# 2_Non_Volatile_Memories.net
KiCad netlist of a schematic drawn in Altium Designer
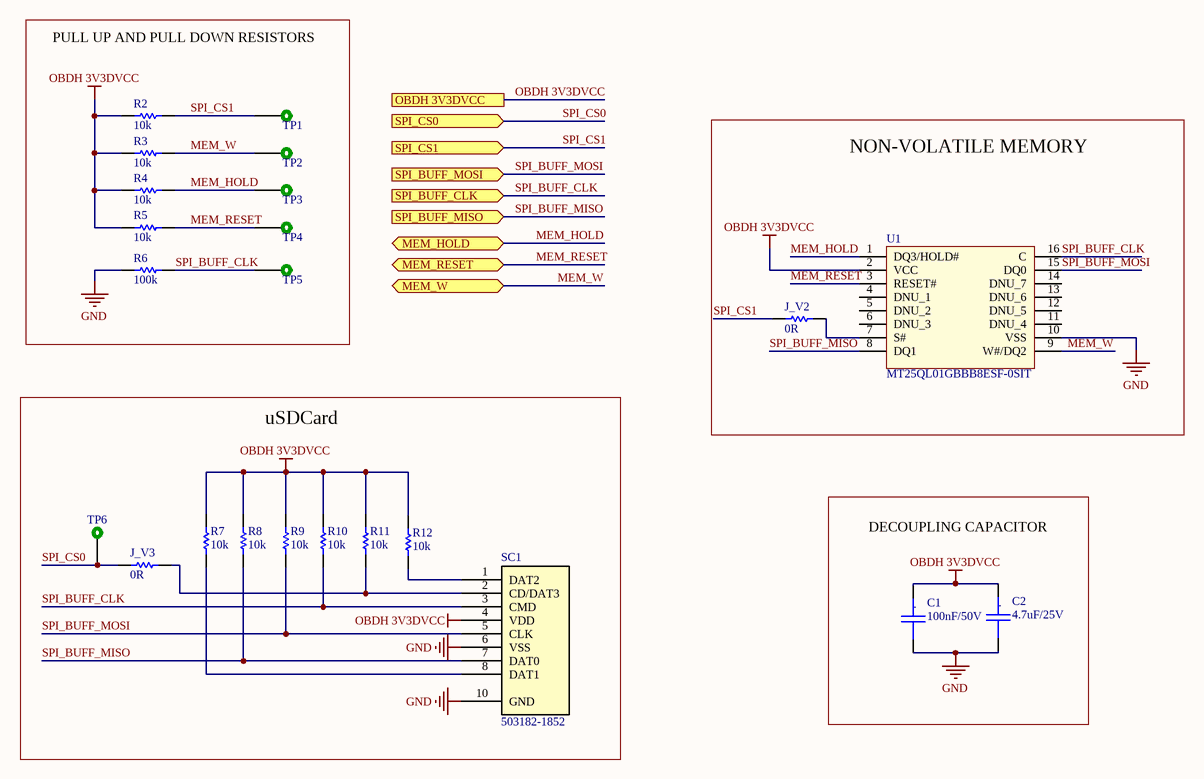
[diagram p0: 2_Non_Volatile_Memories.SchDoc]

(export (version "E")
  (design (tool "Eeschema 10.0.6"))
  (components
    (comp (ref "C1")
      (value "100nF/50V")
      (footprint "C0603_MD")
      (description "CAP CER 100nF 50V 0603 10%")
      (fields (field (name "PARTNUMBER") "C0603C104K5RAC3121") (field (name "MANUFACTURER") "Yageo"))
      (libsource (lib "Memory_Expansion_Daughter_Board_SchLib") (part "Cap_Cer_X7R_100nF_50V_0603"))
    )
    (comp (ref "C2")
      (value "4.7uF/25V")
      (footprint "C0805_MD")
      (description "CAP CER 4.7UF 25V 10% X7R 0805")
      (fields (field (name "PARTNUMBER") "C0805C475K3RACAUTO") (field (name "MANUFACTURER") "Taiyo Yuden"))
      (libsource (lib "Memory_Expansion_Daughter_Board_SchLib") (part "Cap_Cer_X7R_4.7uF_25V_0805"))
    )
    (comp (ref "J_V2")
      (value "0R")
      (footprint "0805")
      (description "RES 0R OHM 1/8W JUMPER 0805")
      (fields (field (name "PARTNUMBER") "CRCW08050000Z0EA") (field (name "MANUFACTURER") "Yageo"))
      (libsource (lib "Memory_Expansion_Daughter_Board_SchLib") (part "RC0805JR-070RL"))
    )
    (comp (ref "J_V3")
      (value "0R")
      (footprint "0805")
      (description "RES 0R OHM 1/8W JUMPER 0805")
      (fields (field (name "PARTNUMBER") "CRCW08050000Z0EA") (field (name "MANUFACTURER") "Yageo"))
      (libsource (lib "Memory_Expansion_Daughter_Board_SchLib") (part "RC0805JR-070RL"))
    )
    (comp (ref "R2")
      (value "10k")
      (footprint "0805")
      (description "RES 10K OHM 1/8W 1%  0805")
      (fields (field (name "PARTNUMBER") "CRCW080510K0FKEA") (field (name "MANUFACTURER") "Vishay"))
      (libsource (lib "Memory_Expansion_Daughter_Board_SchLib") (part "R10k_1%_1/8W_0805"))
    )
    (comp (ref "R3")
      (value "10k")
      (footprint "0805")
      (description "RES 10K OHM 1/8W 1%  0805")
      (fields (field (name "PARTNUMBER") "CRCW080510K0FKEA") (field (name "MANUFACTURER") "Vishay"))
      (libsource (lib "Memory_Expansion_Daughter_Board_SchLib") (part "R10k_1%_1/8W_0805"))
    )
    (comp (ref "R4")
      (value "10k")
      (footprint "0805")
      (description "RES 10K OHM 1/8W 1%  0805")
      (fields (field (name "PARTNUMBER") "CRCW080510K0FKEA") (field (name "MANUFACTURER") "Vishay"))
      (libsource (lib "Memory_Expansion_Daughter_Board_SchLib") (part "R10k_1%_1/8W_0805"))
    )
    (comp (ref "R5")
      (value "10k")
      (footprint "0805")
      (description "RES 10K OHM 1/8W 1%  0805")
      (fields (field (name "PARTNUMBER") "CRCW080510K0FKEA") (field (name "MANUFACTURER") "Vishay"))
      (libsource (lib "Memory_Expansion_Daughter_Board_SchLib") (part "R10k_1%_1/8W_0805"))
    )
    (comp (ref "R6")
      (value "100k")
      (footprint "0805")
      (description "RES 100K OHM 1/8W 1% 0805")
      (fields (field (name "PARTNUMBER") "AC0805FR-13100KL") (field (name "MANUFACTURER") "Yageo"))
      (libsource (lib "Memory_Expansion_Daughter_Board_SchLib") (part "R100k_1%_1/8W_0805"))
    )
    (comp (ref "R7")
      (value "10k")
      (footprint "0805")
      (description "RES 10K OHM 1/8W 1%  0805")
      (fields (field (name "PARTNUMBER") "CRCW080510K0FKEA") (field (name "MANUFACTURER") "Vishay"))
      (libsource (lib "Memory_Expansion_Daughter_Board_SchLib") (part "R10k_1%_1/8W_0805"))
    )
    (comp (ref "R8")
      (value "10k")
      (footprint "0805")
      (description "RES 10K OHM 1/8W 1%  0805")
      (fields (field (name "PARTNUMBER") "CRCW080510K0FKEA") (field (name "MANUFACTURER") "Vishay"))
      (libsource (lib "Memory_Expansion_Daughter_Board_SchLib") (part "R10k_1%_1/8W_0805"))
    )
    (comp (ref "R9")
      (value "10k")
      (footprint "0805")
      (description "RES 10K OHM 1/8W 1%  0805")
      (fields (field (name "PARTNUMBER") "CRCW080510K0FKEA") (field (name "MANUFACTURER") "Vishay"))
      (libsource (lib "Memory_Expansion_Daughter_Board_SchLib") (part "R10k_1%_1/8W_0805"))
    )
    (comp (ref "R10")
      (value "10k")
      (footprint "0805")
      (description "RES 10K OHM 1/8W 1%  0805")
      (fields (field (name "PARTNUMBER") "CRCW080510K0FKEA") (field (name "MANUFACTURER") "Vishay"))
      (libsource (lib "Memory_Expansion_Daughter_Board_SchLib") (part "R10k_1%_1/8W_0805"))
    )
    (comp (ref "R11")
      (value "10k")
      (footprint "0805")
      (description "RES 10K OHM 1/8W 1%  0805")
      (fields (field (name "PARTNUMBER") "CRCW080510K0FKEA") (field (name "MANUFACTURER") "Vishay"))
      (libsource (lib "Memory_Expansion_Daughter_Board_SchLib") (part "R10k_1%_1/8W_0805"))
    )
    (comp (ref "R12")
      (value "10k")
      (footprint "0805")
      (description "RES 10K OHM 1/8W 1%  0805")
      (fields (field (name "PARTNUMBER") "CRCW080510K0FKEA") (field (name "MANUFACTURER") "Vishay"))
      (libsource (lib "Memory_Expansion_Daughter_Board_SchLib") (part "R10k_1%_1/8W_0805"))
    )
    (comp (ref "SC1")
      (value "MicroSD Card Connector")
      (footprint "USD_CARD")
      (description "MOLEX - 503182-1852 - Micro SD Normal UltraLowPro8CktEmbsTpPkg RoHS Compliant: Yes")
      (fields (field (name "MANUFACTURER") "Molex") (field (name "MANUFACTURER PART NUMBER") "503182-1852"))
      (libsource (lib "Memory_Expansion_Daughter_Board_SchLib") (part "503182-1852"))
    )
    (comp (ref "TP1")
      (value "TEST_POINT_2")
      (footprint "TEST_POINT_2")
      (description "Test point")
      (libsource (lib "Memory_Expansion_Daughter_Board_SchLib") (part "TEST_POINT_2"))
    )
    (comp (ref "TP2")
      (value "TEST_POINT_2")
      (footprint "TEST_POINT_2")
      (description "Test point")
      (libsource (lib "Memory_Expansion_Daughter_Board_SchLib") (part "TEST_POINT_2"))
    )
    (comp (ref "TP3")
      (value "TEST_POINT_2")
      (footprint "TEST_POINT_2")
      (description "Test point")
      (libsource (lib "Memory_Expansion_Daughter_Board_SchLib") (part "TEST_POINT_2"))
    )
    (comp (ref "TP4")
      (value "TEST_POINT_2")
      (footprint "TEST_POINT_2")
      (description "Test point")
      (libsource (lib "Memory_Expansion_Daughter_Board_SchLib") (part "TEST_POINT_2"))
    )
    (comp (ref "TP5")
      (value "TEST_POINT_2")
      (footprint "TEST_POINT_2")
      (description "Test point")
      (libsource (lib "Memory_Expansion_Daughter_Board_SchLib") (part "TEST_POINT_2"))
    )
    (comp (ref "TP6")
      (value "TEST_POINT_2")
      (footprint "TEST_POINT_2")
      (description "Test point")
      (libsource (lib "Memory_Expansion_Daughter_Board_SchLib") (part "TEST_POINT_2"))
    )
    (comp (ref "U1")
      (value "MT25QL01GBBB8ESF-0SIT")
      (footprint "SOIC127P1032X265-16N")
      (description "NOR Flash Serial-SPI 3V 1Gbit 1024M/512M/256M x 1bit/2bit/4bit 6ns 16-Pin SOP-II")
      (fields
        (field (name "MANUFACTURER") "Micron Technology")
        (field (name "MANUFACTURER PART NUMBER") "MT25QL01GBBB8ESF-0SIT")
      )
      (libsource (lib "Memory_Expansion_Daughter_Board_SchLib") (part "MT25QL01GBBB8ESF-0SIT (2)"))
    )
  )
  (nets
    (net (code "1") (name "/MEM_HOLD") (class "Default")
      (node (ref "R4") (pin "1") (pinfunction "1_1") (pintype "passive"))
      (node (ref "TP3") (pin "1") (pinfunction "1_1") (pintype "passive"))
      (node (ref "U1") (pin "1") (pinfunction "DQ3/HOLD#_1") (pintype "passive"))
    )
    (net (code "2") (name "/MEM_RESET") (class "Default")
      (node (ref "R5") (pin "1") (pinfunction "1_1") (pintype "passive"))
      (node (ref "TP4") (pin "1") (pinfunction "1_1") (pintype "passive"))
      (node (ref "U1") (pin "3") (pinfunction "RESET#_3") (pintype "passive"))
    )
    (net (code "3") (name "/MEM_W") (class "Default")
      (node (ref "R3") (pin "1") (pinfunction "1_1") (pintype "passive"))
      (node (ref "TP2") (pin "1") (pinfunction "1_1") (pintype "passive"))
      (node (ref "U1") (pin "9") (pinfunction "W#/DQ2_9") (pintype "passive"))
    )
    (net (code "4") (name "/SPI_BUFF_CLK") (class "Default")
      (node (ref "R10") (pin "1") (pinfunction "1_1") (pintype "passive"))
      (node (ref "R6") (pin "1") (pinfunction "1_1") (pintype "passive"))
      (node (ref "SC1") (pin "3") (pinfunction "CMD_3") (pintype "passive"))
      (node (ref "TP5") (pin "1") (pinfunction "1_1") (pintype "passive"))
      (node (ref "U1") (pin "16") (pinfunction "C_16") (pintype "passive"))
    )
    (net (code "5") (name "/SPI_BUFF_MISO") (class "Default")
      (node (ref "R8") (pin "1") (pinfunction "1_1") (pintype "passive"))
      (node (ref "SC1") (pin "7") (pinfunction "DAT0_7") (pintype "passive"))
      (node (ref "U1") (pin "8") (pinfunction "DQ1_8") (pintype "passive"))
    )
    (net (code "6") (name "/SPI_BUFF_MOSI") (class "Default")
      (node (ref "R9") (pin "1") (pinfunction "1_1") (pintype "passive"))
      (node (ref "SC1") (pin "5") (pinfunction "CLK_5") (pintype "passive"))
      (node (ref "U1") (pin "15") (pinfunction "DQ0_15") (pintype "passive"))
    )
    (net (code "7") (name "/SPI_CS0") (class "Default")
      (node (ref "J_V3") (pin "2") (pinfunction "2_2") (pintype "passive"))
      (node (ref "TP6") (pin "1") (pinfunction "1_1") (pintype "passive"))
    )
    (net (code "8") (name "/SPI_CS1") (class "Default")
      (node (ref "J_V2") (pin "2") (pinfunction "2_2") (pintype "passive"))
      (node (ref "R2") (pin "1") (pinfunction "1_1") (pintype "passive"))
      (node (ref "TP1") (pin "1") (pinfunction "1_1") (pintype "passive"))
    )
    (net (code "9") (name "GND") (class "Default")
      (node (ref "C1") (pin "2") (pinfunction "2_2") (pintype "passive"))
      (node (ref "C2") (pin "2") (pinfunction "2_2") (pintype "passive"))
      (node (ref "R6") (pin "2") (pinfunction "2_2") (pintype "passive"))
      (node (ref "SC1") (pin "10") (pinfunction "GND_10") (pintype "passive"))
      (node (ref "SC1") (pin "6") (pinfunction "VSS_6") (pintype "passive"))
      (node (ref "U1") (pin "10") (pinfunction "VSS_10") (pintype "passive"))
    )
    (net (code "10") (name "Net-(SC1-CD{slash}DAT3)") (class "Default")
      (node (ref "J_V3") (pin "1") (pinfunction "1_1") (pintype "passive"))
      (node (ref "R11") (pin "1") (pinfunction "1_1") (pintype "passive"))
      (node (ref "SC1") (pin "2") (pinfunction "CD/DAT3_2") (pintype "passive"))
    )
    (net (code "11") (name "Net-(SC1-DAT1)") (class "Default")
      (node (ref "R7") (pin "1") (pinfunction "1_1") (pintype "passive"))
      (node (ref "SC1") (pin "8") (pinfunction "DAT1_8") (pintype "passive"))
    )
    (net (code "12") (name "Net-(SC1-DAT2)") (class "Default")
      (node (ref "R12") (pin "1") (pinfunction "1_1") (pintype "passive"))
      (node (ref "SC1") (pin "1") (pinfunction "DAT2_1") (pintype "passive"))
    )
    (net (code "13") (name "Net-(U1-S#)") (class "Default")
      (node (ref "J_V2") (pin "1") (pinfunction "1_1") (pintype "passive"))
      (node (ref "U1") (pin "7") (pinfunction "S#_7") (pintype "passive"))
    )
    (net (code "14") (name "OBDH 3V3DVCC") (class "Default")
      (node (ref "C1") (pin "1") (pinfunction "1_1") (pintype "passive"))
      (node (ref "C2") (pin "1") (pinfunction "1_1") (pintype "passive"))
      (node (ref "R10") (pin "2") (pinfunction "2_2") (pintype "passive"))
      (node (ref "R11") (pin "2") (pinfunction "2_2") (pintype "passive"))
      (node (ref "R12") (pin "2") (pinfunction "2_2") (pintype "passive"))
      (node (ref "R2") (pin "2") (pinfunction "2_2") (pintype "passive"))
      (node (ref "R3") (pin "2") (pinfunction "2_2") (pintype "passive"))
      (node (ref "R4") (pin "2") (pinfunction "2_2") (pintype "passive"))
      (node (ref "R5") (pin "2") (pinfunction "2_2") (pintype "passive"))
      (node (ref "R7") (pin "2") (pinfunction "2_2") (pintype "passive"))
      (node (ref "R8") (pin "2") (pinfunction "2_2") (pintype "passive"))
      (node (ref "R9") (pin "2") (pinfunction "2_2") (pintype "passive"))
      (node (ref "SC1") (pin "4") (pinfunction "VDD_4") (pintype "passive"))
      (node (ref "U1") (pin "2") (pinfunction "VCC_2") (pintype "passive"))
    )
    (net (code "15") (name "unconnected-(U1-DNU_1-Pad4)") (class "Default")
      (node (ref "U1") (pin "4") (pinfunction "DNU_1_4") (pintype "passive"))
    )
    (net (code "16") (name "unconnected-(U1-DNU_2-Pad5)") (class "Default")
      (node (ref "U1") (pin "5") (pinfunction "DNU_2_5") (pintype "passive"))
    )
    (net (code "17") (name "unconnected-(U1-DNU_3-Pad6)") (class "Default")
      (node (ref "U1") (pin "6") (pinfunction "DNU_3_6") (pintype "passive"))
    )
    (net (code "18") (name "unconnected-(U1-DNU_4-Pad11)") (class "Default")
      (node (ref "U1") (pin "11") (pinfunction "DNU_4_11") (pintype "passive"))
    )
    (net (code "19") (name "unconnected-(U1-DNU_5-Pad12)") (class "Default")
      (node (ref "U1") (pin "12") (pinfunction "DNU_5_12") (pintype "passive"))
    )
    (net (code "20") (name "unconnected-(U1-DNU_6-Pad13)") (class "Default")
      (node (ref "U1") (pin "13") (pinfunction "DNU_6_13") (pintype "passive"))
    )
    (net (code "21") (name "unconnected-(U1-DNU_7-Pad14)") (class "Default")
      (node (ref "U1") (pin "14") (pinfunction "DNU_7_14") (pintype "passive"))
    )
  )
)
